# P3V3_PP5V_GESTION.net
KiCad netlist of a schematic drawn in Altium Designer
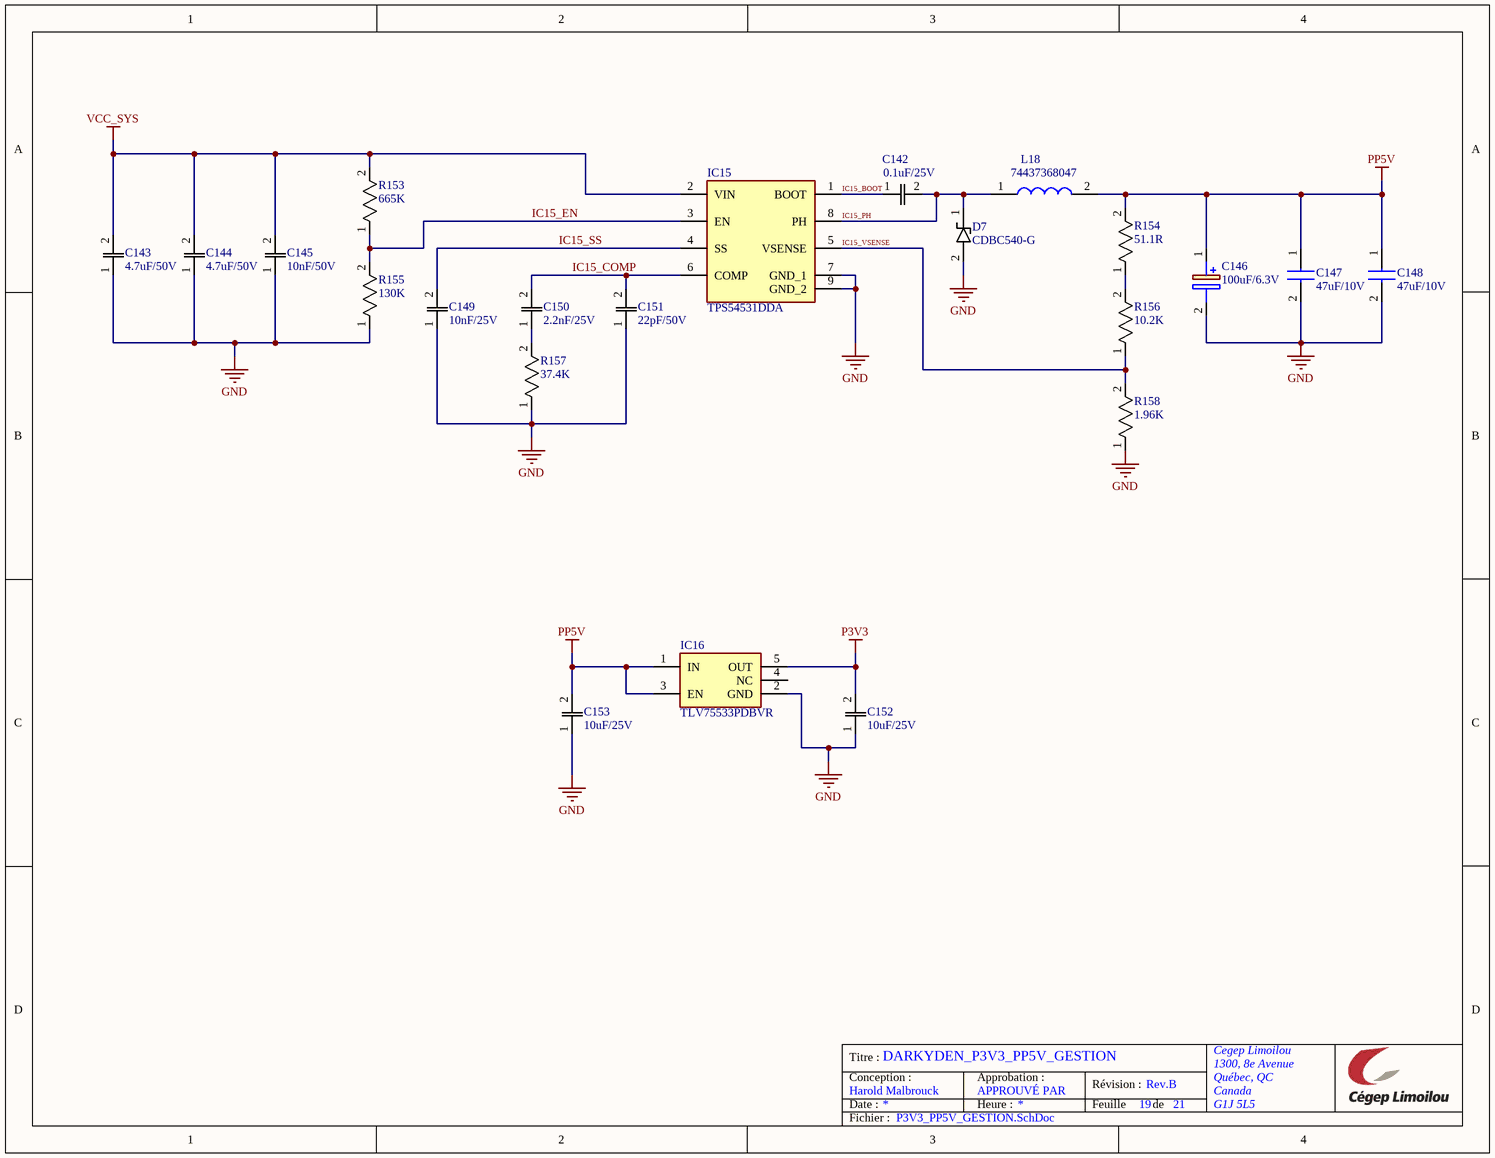
[diagram p0: P3V3_PP5V_GESTION.SchDoc]

(export (version "E")
  (design (tool "Eeschema 10.0.6"))
  (components
    (comp (ref "C142")
      (value "0.1uF/25V")
      (footprint "c0805")
      (description "0.1uF 25V X7R 10% SMD 0805 125C Plastic T/R")
      (fields
        (field (name "MANUFACTURER") "KEMET")
        (field (name "MANUFACTURER PART NUMBER") "C0805C104K5RACTU")
      )
      (libsource (lib "DARKYDEN") (part "C0805C104K3RACTU"))
    )
    (comp (ref "C143")
      (value "4.7uF/50V")
      (footprint "c0805")
      (description "4.7uF/50V X5R 卤10% 0805 Multilayer Ceramic Capacitors MLCC - SMD/SMT ROHS")
      (fields
        (field (name "MANUFACTURER") "TDK")
        (field (name "MANUFACTURER PART NUMBER") "CGA4J3X5R1H475K125AB")
      )
      (libsource (lib "DARKYDEN") (part "CGA4J3X5R1H475K125AB"))
    )
    (comp (ref "C144")
      (value "4.7uF/50V")
      (footprint "c0805")
      (description "4.7uF/50V X5R 卤10% 0805 Multilayer Ceramic Capacitors MLCC - SMD/SMT ROHS")
      (fields
        (field (name "MANUFACTURER") "TDK")
        (field (name "MANUFACTURER PART NUMBER") "CGA4J3X5R1H475K125AB")
      )
      (libsource (lib "DARKYDEN") (part "CGA4J3X5R1H475K125AB"))
    )
    (comp (ref "C145")
      (value "10nF/50V")
      (footprint "c0805")
      (description "10nF/50V X7R 0805 10%")
      (fields
        (field (name "MANUFACTURER") "KEMET")
        (field (name "MANUFACTURER PART NUMBER") "C0805C103K5RACTU")
      )
      (libsource (lib "DARKYDEN") (part "C0805C103K5RACTU"))
    )
    (comp (ref "C146")
      (value "100uF/6.3V")
      (footprint "SamacSys:T520B")
      (description "100uF / 6.3VDC B CASE 20%  Cap Tant Polymer SMD 3528-21 0.015 Ohm 105C T/R")
      (fields
        (field (name "MOUSER PART NUMBER") "80-T520B107M6ATE15")
        (field (name "ARROW PART NUMBER") "T520B107M006ATE015")
      )
      (libsource (lib "SamacSys") (part "T520B107M006ATE015"))
    )
    (comp (ref "C147")
      (value "47uF/10V")
      (footprint "SamacSys:CAPC3225X270N")
      (description "Multilayer Ceramic Capacitor, 47 uF, 10 V, ï¿½ 10%, X5R, 1210 [3225 Metric]")
      (fields
        (field (name "MOUSER PART NUMBER") "81-GRM32ER61A476KE20")
        (field (name "ARROW PART NUMBER") "GRM32ER61A476KE20L")
      )
      (libsource (lib "SamacSys") (part "GRM32ER61A476KE20L"))
    )
    (comp (ref "C148")
      (value "47uF/10V")
      (footprint "SamacSys:CAPC3225X270N")
      (description "Multilayer Ceramic Capacitor, 47 uF, 10 V, ï¿½ 10%, X5R, 1210 [3225 Metric]")
      (fields
        (field (name "MOUSER PART NUMBER") "81-GRM32ER61A476KE20")
        (field (name "ARROW PART NUMBER") "GRM32ER61A476KE20L")
      )
      (libsource (lib "SamacSys") (part "GRM32ER61A476KE20L"))
    )
    (comp (ref "C149")
      (value "10nF/25V")
      (footprint "C0805")
      (description "0.01uF 25V X7R 10% SMD 0805 125C Paper T/R")
      (fields
        (field (name "MOUSER PART NUMBER") "80-C0805C103K3R")
        (field (name "ARROW PART NUMBER") "C0805C103K3RACTU")
      )
      (libsource (lib "DARKYDEN") (part "C0805C103K3RACTU"))
    )
    (comp (ref "C150")
      (value "2.2nF/25V")
      (footprint "C0805")
      (description "2.2nF ±10% 25V Ceramic Capacitor C0G, NP0 0805 (2012 Metric)")
      (fields
        (field (name "MANUFACTURER") "KEMET")
        (field (name "MANUFACTURER PART NUMBER") "C0805C222K3GECTU")
      )
      (libsource (lib "DARKYDEN") (part "C0805C222K3GECTU"))
    )
    (comp (ref "C151")
      (value "22pF/50V")
      (footprint "C0805")
      (description "Cap Ceramic 22pF 50V X7R 5% Pad SMD 0805 125°C T/R")
      (fields
        (field (name "MANUFACTURER") "KEMET")
        (field (name "MANUFACTURER PART NUMBER") "C0805C220J5RACTU")
      )
      (libsource (lib "DARKYDEN") (part "C0805C220J5RACTU"))
    )
    (comp (ref "C152")
      (value "10uF/25V")
      (footprint "C0805")
      (description "10uF / 25 VDC, +85degC, X5R Dielec, +/-10% ¦ KEMET C0805C106K3PACTU 0805")
      (fields
        (field (name "MANUFACTURER") "KEMET")
        (field (name "MANUFACTURER PART NUMBER") "C0805C106K3PACTU")
      )
      (libsource (lib "DARKYDEN") (part "C0805C106K3PACTU"))
    )
    (comp (ref "C153")
      (value "10uF/25V")
      (footprint "C0805")
      (description "10uF / 25 VDC, +85degC, X5R Dielec, +/-10% ¦ KEMET C0805C106K3PACTU 0805")
      (fields
        (field (name "MANUFACTURER") "KEMET")
        (field (name "MANUFACTURER PART NUMBER") "C0805C106K3PACTU")
      )
      (libsource (lib "DARKYDEN") (part "C0805C106K3PACTU"))
    )
    (comp (ref "D7")
      (value "CDBC540-G")
      (footprint "SamacSys:DIOM8059X290N")
      (description "Schottky Diode 40V 5A 2-Pin DO-214AB (SMC) CDBC540-G SMT")
      (fields (field (name "MOUSER PART NUMBER") "750-CDBC540-G") (field (name "MANUFACTURER") "Comchip"))
      (libsource (lib "SamacSys") (part "CDBC540-G"))
    )
    (comp (ref "IC15")
      (value "TPS54531DDA")
      (footprint "SamacSys:SOIC127P600X170-9N")
      (fields (field (name "MOUSER PART NUMBER") "595-TPS54531DDA"))
      (libsource (lib "SamacSys") (part "TPS54531DDA"))
    )
    (comp (ref "IC16")
      (value "TLV75533PDBVR")
      (footprint "SamacSys:SOT95P280X145-5N")
      (description "500mA high-PSRR low-IQ low-dropout voltage regulator with enable 5-SOT-23 -40 to 125")
      (fields
        (field (name "MOUSER PART NUMBER") "595-TLV75533PDBVR")
        (field (name "MANUFACTURER") "Texas Instruments")
      )
      (libsource (lib "SamacSys") (part "TLV75533PDBVR"))
    )
    (comp (ref "L18")
      (value "74437368047")
      (footprint "SamacSys:WE-LHMI_104048")
      (fields
        (field (name "MOUSER PART NUMBER") "710-74437368047")
        (field (name "MANUFACTURER") "Wurth Electronics")
        (field (name "TOLERANCE") "20%")
      )
      (libsource (lib "SamacSys") (part "74437368047"))
    )
    (comp (ref "R153")
      (value "665K")
      (footprint "RESC1608X55N")
      (description "665 kOhm, ± 1%, 100 mW, 0603 [1608 Metric], Thick Film, Precision")
      (fields
        (field (name "MANUFACTURER") "Panasonic")
        (field (name "MANUFACTURER PART NUMBER") "ERJ-3EKF6653V")
      )
      (libsource (lib "DARKYDEN") (part "ERJ-3EKF6653V"))
    )
    (comp (ref "R154")
      (value "51.1R")
      (footprint "SamacSys:RESC1608X55N")
      (description "51.1 Ohm 1% 0.1W(1/10W) ±100ppm/C Pad SMD T/R Automotive AEC-Q200")
      (fields
        (field (name "MOUSER PART NUMBER") "667-ERJ-3EKF51R1V")
        (field (name "ARROW PART NUMBER") "ERJ-3EKF51R1V")
      )
      (libsource (lib "DARKYDEN") (part "ERJ-3EKF51R1V"))
    )
    (comp (ref "R155")
      (value "130K")
      (footprint "RESC1608X55N")
      (description "130K Ohm 1% 0.1W Res Thick Film 0603 ±100ppm/°C Molded SMD Punched Carrier T/R")
      (fields
        (field (name "MANUFACTURER") "Panasonic")
        (field (name "MANUFACTURER PART NUMBER") "ERJ-3EKF1303V")
      )
      (libsource (lib "DARKYDEN") (part "ERJ-3EKF1303V"))
    )
    (comp (ref "R156")
      (value "10.2K")
      (footprint "SamacSys:RESC1608X55N")
      (description "10.2 kOhm, ± 1%, 100 mW, 0603 [1608 Metric], Thick Film, Precision")
      (fields
        (field (name "MOUSER PART NUMBER") "667-ERJ-3EKF1022V")
        (field (name "ARROW PART NUMBER") "ERJ-3EKF1022V")
      )
      (libsource (lib "DARKYDEN") (part "ERJ-3EKF1022V"))
    )
    (comp (ref "R157")
      (value "37.4K")
      (footprint "RESC1608X55N")
      (description "37.4K Ohm 1% 1/10W ±100ppm/°C Molded SMD Punched Carrier T/R")
      (fields
        (field (name "MANUFACTURER") "Panasonic")
        (field (name "MANUFACTURER PART NUMBER") "ERJ-3EKF3742V")
      )
      (libsource (lib "DARKYDEN") (part "ERJ-3EKF3742V"))
    )
    (comp (ref "R158")
      (value "1.96K")
      (footprint "RESC1608X55N")
      (description "1.96K Ohm 1% 1/10W ±100ppm/°C Molded SMD Punched Carrier T/R")
      (fields
        (field (name "MANUFACTURER") "Panasonic")
        (field (name "MANUFACTURER PART NUMBER") "ERJ-3EKF1961V")
      )
      (libsource (lib "DARKYDEN") (part "ERJ-3EKF1961V"))
    )
  )
  (nets
    (net (code "1") (name "/IC15_BOOT") (class "Default")
      (node (ref "C142") (pin "1") (pinfunction "1_1") (pintype "passive"))
      (node (ref "IC15") (pin "1") (pinfunction "BOOT_1") (pintype "passive"))
    )
    (net (code "2") (name "/IC15_COMP") (class "Default")
      (node (ref "C150") (pin "2") (pinfunction "2_2") (pintype "passive"))
      (node (ref "C151") (pin "2") (pinfunction "2_2") (pintype "passive"))
      (node (ref "IC15") (pin "6") (pinfunction "COMP_6") (pintype "passive"))
    )
    (net (code "3") (name "/IC15_EN") (class "Default")
      (node (ref "IC15") (pin "3") (pinfunction "EN_3") (pintype "passive"))
      (node (ref "R153") (pin "1") (pinfunction "1_1") (pintype "passive"))
      (node (ref "R155") (pin "2") (pinfunction "2_2") (pintype "passive"))
    )
    (net (code "4") (name "/IC15_PH") (class "Default")
      (node (ref "C142") (pin "2") (pinfunction "2_2") (pintype "passive"))
      (node (ref "D7") (pin "1") (pinfunction "K_1") (pintype "passive"))
      (node (ref "IC15") (pin "8") (pinfunction "PH_8") (pintype "passive"))
      (node (ref "L18") (pin "1") (pinfunction "1_1") (pintype "passive"))
    )
    (net (code "5") (name "/IC15_SS") (class "Default")
      (node (ref "C149") (pin "2") (pinfunction "2_2") (pintype "passive"))
      (node (ref "IC15") (pin "4") (pinfunction "SS_4") (pintype "passive"))
    )
    (net (code "6") (name "/IC15_VSENSE") (class "Default")
      (node (ref "IC15") (pin "5") (pinfunction "VSENSE_5") (pintype "passive"))
      (node (ref "R156") (pin "1") (pinfunction "1_1") (pintype "passive"))
      (node (ref "R158") (pin "2") (pinfunction "2_2") (pintype "passive"))
    )
    (net (code "7") (name "GND") (class "Default")
      (node (ref "C143") (pin "1") (pinfunction "1_1") (pintype "passive"))
      (node (ref "C144") (pin "1") (pinfunction "1_1") (pintype "passive"))
      (node (ref "C145") (pin "1") (pinfunction "1_1") (pintype "passive"))
      (node (ref "C146") (pin "2") (pinfunction "-_2") (pintype "passive"))
      (node (ref "C147") (pin "2") (pinfunction "2_2") (pintype "passive"))
      (node (ref "C148") (pin "2") (pinfunction "2_2") (pintype "passive"))
      (node (ref "C149") (pin "1") (pinfunction "1_1") (pintype "passive"))
      (node (ref "C151") (pin "1") (pinfunction "1_1") (pintype "passive"))
      (node (ref "C152") (pin "1") (pinfunction "1_1") (pintype "passive"))
      (node (ref "C153") (pin "1") (pinfunction "1_1") (pintype "passive"))
      (node (ref "D7") (pin "2") (pinfunction "A_2") (pintype "passive"))
      (node (ref "IC15") (pin "7") (pinfunction "GND_1_7") (pintype "passive"))
      (node (ref "IC15") (pin "9") (pinfunction "GND_2_9") (pintype "passive"))
      (node (ref "IC16") (pin "2") (pinfunction "GND_2") (pintype "passive"))
      (node (ref "R155") (pin "1") (pinfunction "1_1") (pintype "passive"))
      (node (ref "R157") (pin "1") (pinfunction "1_1") (pintype "passive"))
      (node (ref "R158") (pin "1") (pinfunction "1_1") (pintype "passive"))
    )
    (net (code "8") (name "Net-(C150-Pad1)") (class "Default")
      (node (ref "C150") (pin "1") (pinfunction "1_1") (pintype "passive"))
      (node (ref "R157") (pin "2") (pinfunction "2_2") (pintype "passive"))
    )
    (net (code "9") (name "Net-(R154-Pad1)") (class "Default")
      (node (ref "R154") (pin "1") (pinfunction "1_1") (pintype "passive"))
      (node (ref "R156") (pin "2") (pinfunction "2_2") (pintype "passive"))
    )
    (net (code "10") (name "P3V3") (class "Default")
      (node (ref "C152") (pin "2") (pinfunction "2_2") (pintype "passive"))
      (node (ref "IC16") (pin "5") (pinfunction "OUT_5") (pintype "passive"))
    )
    (net (code "11") (name "PP5V") (class "Default")
      (node (ref "C146") (pin "1") (pinfunction "+_1") (pintype "passive"))
      (node (ref "C147") (pin "1") (pinfunction "1_1") (pintype "passive"))
      (node (ref "C148") (pin "1") (pinfunction "1_1") (pintype "passive"))
      (node (ref "C153") (pin "2") (pinfunction "2_2") (pintype "passive"))
      (node (ref "IC16") (pin "1") (pinfunction "IN_1") (pintype "passive"))
      (node (ref "IC16") (pin "3") (pinfunction "EN_3") (pintype "passive"))
      (node (ref "L18") (pin "2") (pinfunction "2_2") (pintype "passive"))
      (node (ref "R154") (pin "2") (pinfunction "2_2") (pintype "passive"))
    )
    (net (code "12") (name "VCC_SYS") (class "Default")
      (node (ref "C143") (pin "2") (pinfunction "2_2") (pintype "passive"))
      (node (ref "C144") (pin "2") (pinfunction "2_2") (pintype "passive"))
      (node (ref "C145") (pin "2") (pinfunction "2_2") (pintype "passive"))
      (node (ref "IC15") (pin "2") (pinfunction "VIN_2") (pintype "passive"))
      (node (ref "R153") (pin "2") (pinfunction "2_2") (pintype "passive"))
    )
    (net (code "13") (name "unconnected-(IC16-NC-Pad4)") (class "Default")
      (node (ref "IC16") (pin "4") (pinfunction "NC_4") (pintype "passive"))
    )
  )
)
